# HighSpeedSlots_x2.net
KiCad netlist of a schematic drawn in Altium Designer
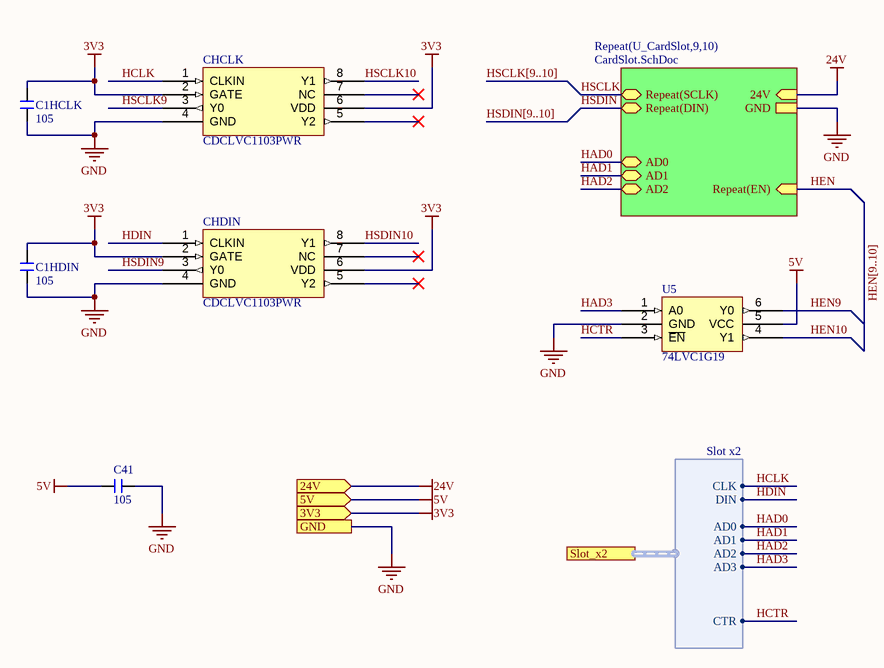
[diagram p0: HighSpeedSlots_x2.SchDoc]

(export (version "E")
  (design (tool "Eeschema 10.0.6"))
  (components
    (comp (ref "C1HCLK")
      (value "105")
      (footprint "C 0603_L")
      (description "贴片电容")
      (libsource (lib "0.1 - 电阻-电容-电感") (part "C"))
    )
    (comp (ref "C1HDIN")
      (value "105")
      (footprint "C 0603_L")
      (description "贴片电容")
      (libsource (lib "0.1 - 电阻-电容-电感") (part "C"))
    )
    (comp (ref "C41")
      (value "105")
      (footprint "C 0603_L")
      (description "贴片电容")
      (libsource (lib "0.1 - 电阻-电容-电感") (part "C"))
    )
    (comp (ref "CHCLK")
      (value "CDCLVC1103PWR")
      (footprint "TSSOP-8-3mm")
      (description "1:3 Clock Fan-out Buffer")
      (libsource (lib "CustomizedComponents") (part "CDCLVC1103PWR"))
    )
    (comp (ref "CHDIN")
      (value "CDCLVC1103PWR")
      (footprint "TSSOP-8-3mm")
      (description "1:3 Clock Fan-out Buffer")
      (libsource (lib "CustomizedComponents") (part "CDCLVC1103PWR"))
    )
    (comp (ref "U5")
      (value "74LVC1G19")
      (footprint "SOT23-6")
      (description "1-to-2 Decoder ActiveLow C58923")
      (libsource (lib "CustomizedComponents") (part "74LVC1G19"))
    )
  )
  (nets
    (net (code "6") (name "/HAD3") (class "Default")
      (node (ref "U5") (pin "1") (pinfunction "A0_1") (pintype "input"))
    )
    (net (code "7") (name "/HCLK") (class "Default")
      (node (ref "CHCLK") (pin "1") (pinfunction "CLKIN_1") (pintype "input"))
    )
    (net (code "8") (name "/HCTR") (class "Default")
      (node (ref "U5") (pin "3") (pinfunction "EN_3") (pintype "input"))
    )
    (net (code "9") (name "/HDIN") (class "Default")
      (node (ref "CHDIN") (pin "1") (pinfunction "CLKIN_1") (pintype "input"))
    )
    (net (code "11") (name "/HEN9") (class "Default")
      (node (ref "U5") (pin "6") (pinfunction "Y0_6") (pintype "output"))
    )
    (net (code "12") (name "/HEN10") (class "Default")
      (node (ref "U5") (pin "4") (pinfunction "Y1_4") (pintype "output"))
    )
    (net (code "15") (name "/HSCLK9") (class "Default")
      (node (ref "CHCLK") (pin "3") (pinfunction "Y0_3") (pintype "output"))
    )
    (net (code "16") (name "/HSCLK10") (class "Default")
      (node (ref "CHCLK") (pin "8") (pinfunction "Y1_8") (pintype "output"))
    )
    (net (code "19") (name "/HSDIN9") (class "Default")
      (node (ref "CHDIN") (pin "3") (pinfunction "Y0_3") (pintype "output"))
    )
    (net (code "20") (name "/HSDIN10") (class "Default")
      (node (ref "CHDIN") (pin "8") (pinfunction "Y1_8") (pintype "output"))
    )
    (net (code "23") (name "3V3") (class "Default")
      (node (ref "C1HCLK") (pin "2") (pinfunction "2_2") (pintype "passive"))
      (node (ref "C1HDIN") (pin "2") (pinfunction "2_2") (pintype "passive"))
      (node (ref "CHCLK") (pin "2") (pinfunction "GATE_2") (pintype "input"))
      (node (ref "CHCLK") (pin "6") (pinfunction "VDD_6") (pintype "power_in"))
      (node (ref "CHDIN") (pin "2") (pinfunction "GATE_2") (pintype "input"))
      (node (ref "CHDIN") (pin "6") (pinfunction "VDD_6") (pintype "power_in"))
    )
    (net (code "24") (name "5V") (class "Default")
      (node (ref "C41") (pin "2") (pinfunction "2_2") (pintype "passive"))
      (node (ref "U5") (pin "5") (pinfunction "VCC_5") (pintype "power_in"))
    )
    (net (code "26") (name "GND") (class "Default")
      (node (ref "C1HCLK") (pin "1") (pinfunction "1_1") (pintype "passive"))
      (node (ref "C1HDIN") (pin "1") (pinfunction "1_1") (pintype "passive"))
      (node (ref "C41") (pin "1") (pinfunction "1_1") (pintype "passive"))
      (node (ref "CHCLK") (pin "4") (pinfunction "GND_4") (pintype "power_in"))
      (node (ref "CHDIN") (pin "4") (pinfunction "GND_4") (pintype "power_in"))
      (node (ref "U5") (pin "2") (pinfunction "GND_2") (pintype "power_in"))
    )
    (net (code "27") (name "unconnected-(CHCLK-NC-Pad7)") (class "Default")
      (node (ref "CHCLK") (pin "7") (pinfunction "NC_7") (pintype "passive+no_connect"))
    )
    (net (code "28") (name "unconnected-(CHCLK-Y2-Pad5)") (class "Default")
      (node (ref "CHCLK") (pin "5") (pinfunction "Y2_5") (pintype "output+no_connect"))
    )
    (net (code "29") (name "unconnected-(CHDIN-NC-Pad7)") (class "Default")
      (node (ref "CHDIN") (pin "7") (pinfunction "NC_7") (pintype "passive+no_connect"))
    )
    (net (code "30") (name "unconnected-(CHDIN-Y2-Pad5)") (class "Default")
      (node (ref "CHDIN") (pin "5") (pinfunction "Y2_5") (pintype "output+no_connect"))
    )
  )
)
